# SAM3X_MCU2.net
KiCad netlist of a schematic drawn in Altium Designer
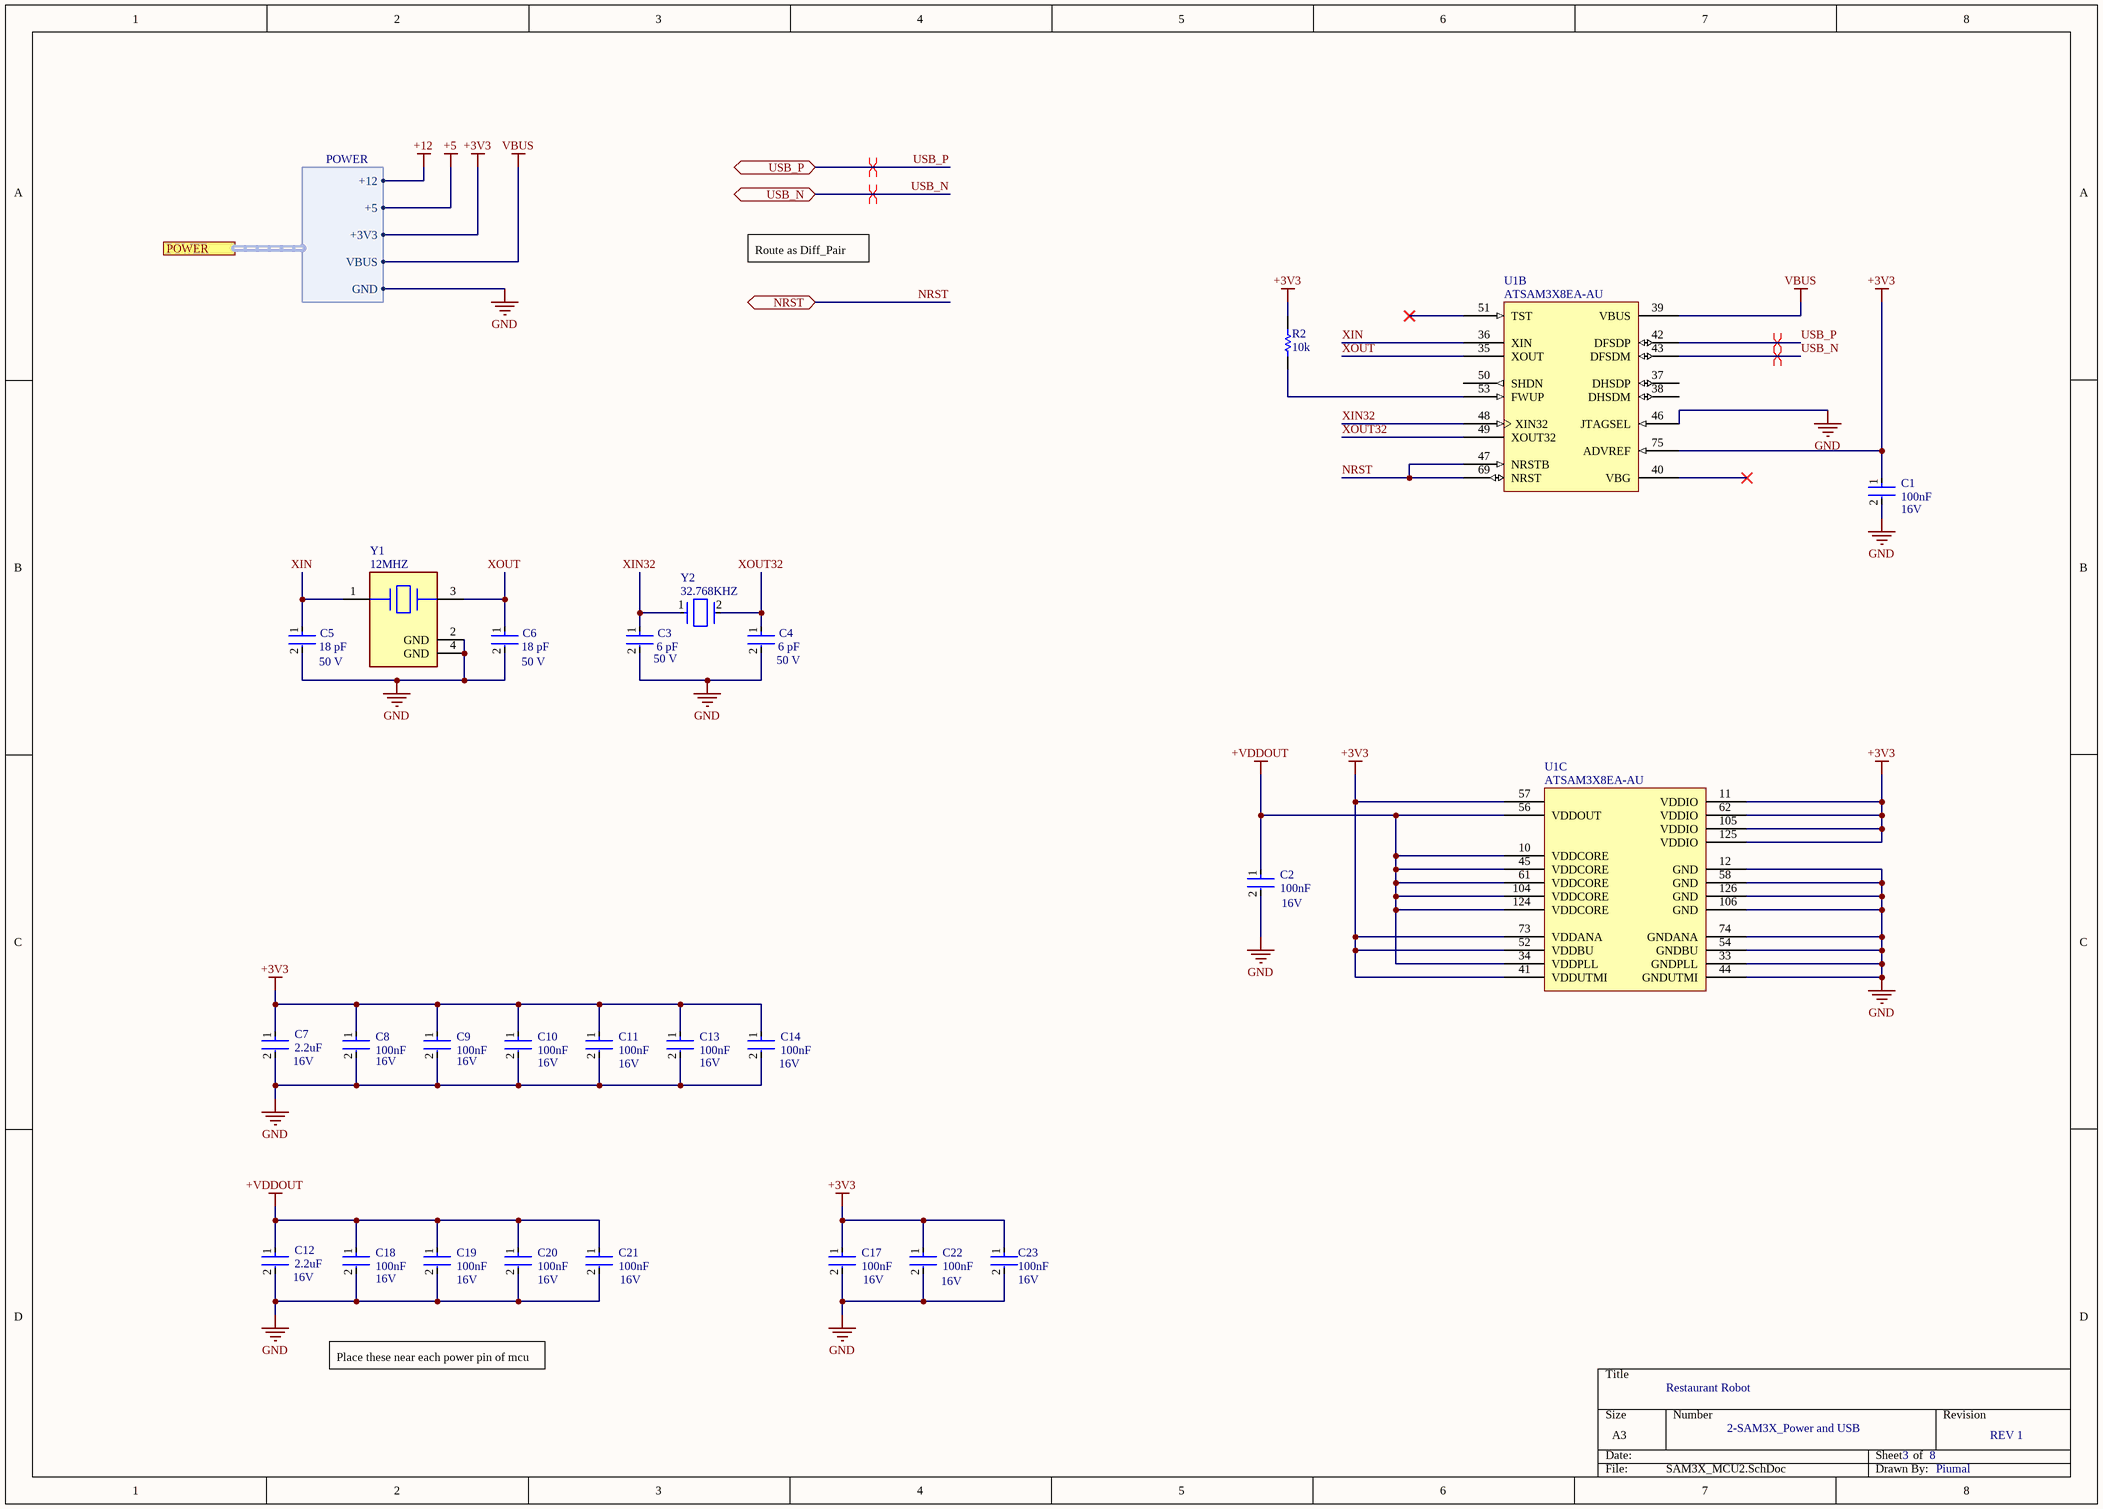
[diagram p0: SAM3X_MCU2.SchDoc]

(export (version "E")
  (design (tool "Eeschema 10.0.6"))
  (components
    (comp (ref "C1")
      (value "CL21B104KOANNNC")
      (footprint "FP-CL21-IPC_A")
      (description "CL21 Series 0805 100nF 16V ±10% Tolerance X7R Multilayer Ceramic Chip Capacitor")
      (fields
        (field (name "VOLTAGE RATING (DC)") "16V")
        (field (name "TOLERANCE") "10%")
        (field (name "CAPACITANCE") "100nF")
      )
      (libsource (lib "Altium Content Vault") (part "b4654b650e69147ec39a6b967a45e02"))
    )
    (comp (ref "C2")
      (value "CL21B104KOANNNC")
      (footprint "FP-CL21-IPC_A")
      (description "CL21 Series 0805 100nF 16V ±10% Tolerance X7R Multilayer Ceramic Chip Capacitor")
      (fields
        (field (name "VOLTAGE RATING (DC)") "16V")
        (field (name "TOLERANCE") "10%")
        (field (name "CAPACITANCE") "100nF")
      )
      (libsource (lib "Altium Content Vault") (part "b4654b650e69147ec39a6b967a45e02"))
    )
    (comp (ref "C3")
      (value "C0805C120J5GACTU")
      (footprint "FP-C0805C-DN-MFG")
      (description "CAP CER 12PF 50V C0G/NP0 0805")
      (fields
        (field (name "MANUFACTURER") "KEMET")
        (field (name "CAPACITANCE") "6 pF")
        (field (name "TOLERANCE") "0.05")
        (field (name "VOLTAGE RATING") "50 V")
      )
      (libsource (lib "Altium Content Vault") (part "b4654b650e69147ec39a6b967a45e02"))
    )
    (comp (ref "C4")
      (value "C0805C120J5GACTU")
      (footprint "FP-C0805C-DN-MFG")
      (description "CAP CER 12PF 50V C0G/NP0 0805")
      (fields
        (field (name "MANUFACTURER") "KEMET")
        (field (name "CAPACITANCE") "6 pF")
        (field (name "TOLERANCE") "0.05")
        (field (name "VOLTAGE RATING") "50 V")
      )
      (libsource (lib "Altium Content Vault") (part "b4654b650e69147ec39a6b967a45e02"))
    )
    (comp (ref "C5")
      (value "C0805C120J5GACTU")
      (footprint "FP-C0805C-DN-MFG")
      (description "CAP CER 12PF 50V C0G/NP0 0805")
      (fields
        (field (name "MANUFACTURER") "KEMET")
        (field (name "CAPACITANCE") "18 pF")
        (field (name "TOLERANCE") "0.05")
        (field (name "VOLTAGE RATING") "50 V")
      )
      (libsource (lib "Altium Content Vault") (part "b4654b650e69147ec39a6b967a45e02"))
    )
    (comp (ref "C6")
      (value "C0805C120J5GACTU")
      (footprint "FP-C0805C-DN-MFG")
      (description "CAP CER 12PF 50V C0G/NP0 0805")
      (fields
        (field (name "MANUFACTURER") "KEMET")
        (field (name "CAPACITANCE") "18 pF")
        (field (name "TOLERANCE") "0.05")
        (field (name "VOLTAGE RATING") "50 V")
      )
      (libsource (lib "Altium Content Vault") (part "b4654b650e69147ec39a6b967a45e02"))
    )
    (comp (ref "C7")
      (value "CL21A225KOFNNNG")
      (footprint "FP-CL21-IPC_A")
      (description "CL21 Series 0805 2.2uF 16V ±10% Tolerance X5R Multilayer Ceramic Chip Capacitor")
      (fields
        (field (name "VOLTAGE RATING") "16V")
        (field (name "TOLERANCE") "10%")
        (field (name "CAPACITANCE") "2.2uF")
      )
      (libsource (lib "Altium Content Vault") (part "b4654b650e69147ec39a6b967a45e02"))
    )
    (comp (ref "C8")
      (value "CL21B104KOANNNC")
      (footprint "FP-CL21-IPC_A")
      (description "CL21 Series 0805 100nF 16V ±10% Tolerance X7R Multilayer Ceramic Chip Capacitor")
      (fields
        (field (name "VOLTAGE RATING (DC)") "16V")
        (field (name "TOLERANCE") "10%")
        (field (name "CAPACITANCE") "100nF")
      )
      (libsource (lib "Altium Content Vault") (part "b4654b650e69147ec39a6b967a45e02"))
    )
    (comp (ref "C9")
      (value "CL21B104KOANNNC")
      (footprint "FP-CL21-IPC_A")
      (description "CL21 Series 0805 100nF 16V ±10% Tolerance X7R Multilayer Ceramic Chip Capacitor")
      (fields
        (field (name "VOLTAGE RATING (DC)") "16V")
        (field (name "TOLERANCE") "10%")
        (field (name "CAPACITANCE") "100nF")
      )
      (libsource (lib "Altium Content Vault") (part "b4654b650e69147ec39a6b967a45e02"))
    )
    (comp (ref "C10")
      (value "CL21B104KOANNNC")
      (footprint "FP-CL21-IPC_A")
      (description "CL21 Series 0805 100nF 16V ±10% Tolerance X7R Multilayer Ceramic Chip Capacitor")
      (fields
        (field (name "VOLTAGE RATING (DC)") "16V")
        (field (name "TOLERANCE") "10%")
        (field (name "CAPACITANCE") "100nF")
      )
      (libsource (lib "Altium Content Vault") (part "b4654b650e69147ec39a6b967a45e02"))
    )
    (comp (ref "C11")
      (value "CL21B104KOANNNC")
      (footprint "FP-CL21-IPC_A")
      (description "CL21 Series 0805 100nF 16V ±10% Tolerance X7R Multilayer Ceramic Chip Capacitor")
      (fields
        (field (name "VOLTAGE RATING (DC)") "16V")
        (field (name "TOLERANCE") "10%")
        (field (name "CAPACITANCE") "100nF")
      )
      (libsource (lib "Altium Content Vault") (part "b4654b650e69147ec39a6b967a45e02"))
    )
    (comp (ref "C12")
      (value "CL21A225KOFNNNG")
      (footprint "FP-CL21-IPC_A")
      (description "CL21 Series 0805 2.2uF 16V ±10% Tolerance X5R Multilayer Ceramic Chip Capacitor")
      (fields
        (field (name "VOLTAGE RATING") "16V")
        (field (name "TOLERANCE") "10%")
        (field (name "CAPACITANCE") "2.2uF")
      )
      (libsource (lib "Altium Content Vault") (part "b4654b650e69147ec39a6b967a45e02"))
    )
    (comp (ref "C13")
      (value "CL21B104KOANNNC")
      (footprint "FP-CL21-IPC_A")
      (description "CL21 Series 0805 100nF 16V ±10% Tolerance X7R Multilayer Ceramic Chip Capacitor")
      (fields
        (field (name "VOLTAGE RATING (DC)") "16V")
        (field (name "TOLERANCE") "10%")
        (field (name "CAPACITANCE") "100nF")
      )
      (libsource (lib "Altium Content Vault") (part "b4654b650e69147ec39a6b967a45e02"))
    )
    (comp (ref "C14")
      (value "CL21B104KOANNNC")
      (footprint "FP-CL21-IPC_A")
      (description "CL21 Series 0805 100nF 16V ±10% Tolerance X7R Multilayer Ceramic Chip Capacitor")
      (fields
        (field (name "VOLTAGE RATING (DC)") "16V")
        (field (name "TOLERANCE") "10%")
        (field (name "CAPACITANCE") "100nF")
      )
      (libsource (lib "Altium Content Vault") (part "b4654b650e69147ec39a6b967a45e02"))
    )
    (comp (ref "C17")
      (value "CL21B104KOANNNC")
      (footprint "FP-CL21-IPC_A")
      (description "CL21 Series 0805 100nF 16V ±10% Tolerance X7R Multilayer Ceramic Chip Capacitor")
      (fields
        (field (name "VOLTAGE RATING (DC)") "16V")
        (field (name "TOLERANCE") "10%")
        (field (name "CAPACITANCE") "100nF")
      )
      (libsource (lib "Altium Content Vault") (part "b4654b650e69147ec39a6b967a45e02"))
    )
    (comp (ref "C18")
      (value "CL21B104KOANNNC")
      (footprint "FP-CL21-IPC_A")
      (description "CL21 Series 0805 100nF 16V ±10% Tolerance X7R Multilayer Ceramic Chip Capacitor")
      (fields
        (field (name "VOLTAGE RATING (DC)") "16V")
        (field (name "TOLERANCE") "10%")
        (field (name "CAPACITANCE") "100nF")
      )
      (libsource (lib "Altium Content Vault") (part "b4654b650e69147ec39a6b967a45e02"))
    )
    (comp (ref "C19")
      (value "CL21B104KOANNNC")
      (footprint "FP-CL21-IPC_A")
      (description "CL21 Series 0805 100nF 16V ±10% Tolerance X7R Multilayer Ceramic Chip Capacitor")
      (fields
        (field (name "VOLTAGE RATING (DC)") "16V")
        (field (name "TOLERANCE") "10%")
        (field (name "CAPACITANCE") "100nF")
      )
      (libsource (lib "Altium Content Vault") (part "b4654b650e69147ec39a6b967a45e02"))
    )
    (comp (ref "C20")
      (value "CL21B104KOANNNC")
      (footprint "FP-CL21-IPC_A")
      (description "CL21 Series 0805 100nF 16V ±10% Tolerance X7R Multilayer Ceramic Chip Capacitor")
      (fields
        (field (name "VOLTAGE RATING (DC)") "16V")
        (field (name "TOLERANCE") "10%")
        (field (name "CAPACITANCE") "100nF")
      )
      (libsource (lib "Altium Content Vault") (part "b4654b650e69147ec39a6b967a45e02"))
    )
    (comp (ref "C21")
      (value "CL21B104KOANNNC")
      (footprint "FP-CL21-IPC_A")
      (description "CL21 Series 0805 100nF 16V ±10% Tolerance X7R Multilayer Ceramic Chip Capacitor")
      (fields
        (field (name "VOLTAGE RATING (DC)") "16V")
        (field (name "TOLERANCE") "10%")
        (field (name "CAPACITANCE") "100nF")
      )
      (libsource (lib "Altium Content Vault") (part "b4654b650e69147ec39a6b967a45e02"))
    )
    (comp (ref "C22")
      (value "CL21B104KOANNNC")
      (footprint "FP-CL21-IPC_A")
      (description "CL21 Series 0805 100nF 16V ±10% Tolerance X7R Multilayer Ceramic Chip Capacitor")
      (fields
        (field (name "VOLTAGE RATING (DC)") "16V")
        (field (name "TOLERANCE") "10%")
        (field (name "CAPACITANCE") "100nF")
      )
      (libsource (lib "Altium Content Vault") (part "b4654b650e69147ec39a6b967a45e02"))
    )
    (comp (ref "C23")
      (value "100nF")
      (footprint "FP-CL21-IPC_A")
      (description "CL21 Series 0805 100nF 16V ±10% Tolerance X7R Multilayer Ceramic Chip Capacitor")
      (fields
        (field (name "VOLTAGE RATING (DC)") "16V")
        (field (name "TOLERANCE") "10%")
        (field (name "Comment") "CL21B104KOANNNC")
      )
      (libsource (lib "Altium Content Vault") (part "b4654b650e69147ec39a6b967a45e02"))
    )
    (comp (ref "R2")
      (value "RC0805JR-0710KL")
      (footprint "RESC2013X60X35ML10T20")
      (description "Chip Resistor, 10 KOhm, +/- 5%, 0.125 W, -55 to 155 degC, 0805 (2012 Metric), RoHS, Tape and Reel")
      (fields (field (name "MANUFACTURER") "Yageo") (field (name "RESISTANCE") "10k"))
      (libsource (lib "Altium Content Vault") (part "RES-2"))
    )
    (comp (ref "U1")
      (value "ATSAM3X8EA-AU")
      (footprint "LQFP144_M")
      (fields (field (name "MANUFACTURER") "Atmel"))
      (libsource (lib "Altium Content Vault") (part "ATML-ATSAM3X-LQFP-144"))
    )
    (comp (ref "Y1")
      (value "12MHZ")
      (footprint "FP-ABM8G-MFG")
      (description "Crystal 12MHz ±20ppm (Tol) ±30ppm (Stability) 18pF FUND 120Ω 4-Pin SMD T/R")
      (fields (field (name "TOLERANCE") "20ppm"))
      (libsource (lib "Altium Content Vault") (part "48e526d86b7f2615d98721063c72f49"))
    )
    (comp (ref "Y2")
      (value "32.768KHZ")
      (footprint "FP-NX3215SA-MFG")
      (description "NX3215SA-32.768K-STD-MUA-14 Parallel - Fundamental Quartz Crystal, 0.032768MHz Nom")
      (libsource (lib "Altium Content Vault") (part "c23a69dc6c9e2f18f2079038eb95dd1"))
    )
  )
  (nets
    (net (code "2") (name "+3V3") (class "Default")
      (node (ref "C1") (pin "1") (pinfunction "1_1") (pintype "passive"))
      (node (ref "C10") (pin "1") (pinfunction "1_1") (pintype "passive"))
      (node (ref "C11") (pin "1") (pinfunction "1_1") (pintype "passive"))
      (node (ref "C13") (pin "1") (pinfunction "1_1") (pintype "passive"))
      (node (ref "C14") (pin "1") (pinfunction "1_1") (pintype "passive"))
      (node (ref "C17") (pin "1") (pinfunction "1_1") (pintype "passive"))
      (node (ref "C22") (pin "1") (pinfunction "1_1") (pintype "passive"))
      (node (ref "C23") (pin "1") (pinfunction "1_1") (pintype "passive"))
      (node (ref "C7") (pin "1") (pinfunction "1_1") (pintype "passive"))
      (node (ref "C8") (pin "1") (pinfunction "1_1") (pintype "passive"))
      (node (ref "C9") (pin "1") (pinfunction "1_1") (pintype "passive"))
      (node (ref "R2") (pin "2") (pinfunction "2_2") (pintype "passive"))
      (node (ref "U1") (pin "105") (pinfunction "VDDIO_105") (pintype "power_in"))
      (node (ref "U1") (pin "11") (pinfunction "VDDIO_11") (pintype "power_in"))
      (node (ref "U1") (pin "125") (pinfunction "VDDIO_125") (pintype "power_in"))
      (node (ref "U1") (pin "41") (pinfunction "VDDUTMI_41") (pintype "power_in"))
      (node (ref "U1") (pin "52") (pinfunction "VDDBU_52") (pintype "power_in"))
      (node (ref "U1") (pin "57") (pinfunction "VDDIN_57") (pintype "power_in"))
      (node (ref "U1") (pin "62") (pinfunction "VDDIO_62") (pintype "power_in"))
      (node (ref "U1") (pin "73") (pinfunction "VDDANA_73") (pintype "power_in"))
      (node (ref "U1") (pin "75") (pinfunction "ADVREF_75") (pintype "input"))
    )
    (net (code "5") (name "+VDDOUT") (class "Default")
      (node (ref "C12") (pin "1") (pinfunction "1_1") (pintype "passive"))
      (node (ref "C18") (pin "1") (pinfunction "1_1") (pintype "passive"))
      (node (ref "C19") (pin "1") (pinfunction "1_1") (pintype "passive"))
      (node (ref "C2") (pin "1") (pinfunction "1_1") (pintype "passive"))
      (node (ref "C20") (pin "1") (pinfunction "1_1") (pintype "passive"))
      (node (ref "C21") (pin "1") (pinfunction "1_1") (pintype "passive"))
      (node (ref "U1") (pin "10") (pinfunction "VDDCORE_10") (pintype "power_in"))
      (node (ref "U1") (pin "104") (pinfunction "VDDCORE_104") (pintype "power_in"))
      (node (ref "U1") (pin "124") (pinfunction "VDDCORE_124") (pintype "power_in"))
      (node (ref "U1") (pin "34") (pinfunction "VDDPLL_34") (pintype "power_in"))
      (node (ref "U1") (pin "45") (pinfunction "VDDCORE_45") (pintype "power_in"))
      (node (ref "U1") (pin "56") (pinfunction "VDDOUT_56") (pintype "power_in"))
      (node (ref "U1") (pin "61") (pinfunction "VDDCORE_61") (pintype "power_in"))
    )
    (net (code "6") (name "/NRST") (class "Default")
      (node (ref "U1") (pin "47") (pinfunction "NRSTB_47") (pintype "input"))
      (node (ref "U1") (pin "69") (pinfunction "NRST_69") (pintype "bidirectional"))
    )
    (net (code "7") (name "/USB_N") (class "Default")
      (node (ref "U1") (pin "43") (pinfunction "DFSDM_43") (pintype "bidirectional"))
    )
    (net (code "8") (name "/USB_P") (class "Default")
      (node (ref "U1") (pin "42") (pinfunction "DFSDP_42") (pintype "bidirectional"))
    )
    (net (code "9") (name "/XIN") (class "Default")
      (node (ref "C5") (pin "1") (pinfunction "1_1") (pintype "passive"))
      (node (ref "U1") (pin "36") (pinfunction "XIN_36") (pintype "passive"))
      (node (ref "Y1") (pin "1") (pinfunction "1_1") (pintype "passive"))
    )
    (net (code "10") (name "/XIN32") (class "Default")
      (node (ref "C3") (pin "1") (pinfunction "1_1") (pintype "passive"))
      (node (ref "U1") (pin "48") (pinfunction "XIN32_48") (pintype "input"))
      (node (ref "Y2") (pin "1") (pinfunction "1_1") (pintype "passive"))
    )
    (net (code "11") (name "/XOUT") (class "Default")
      (node (ref "C6") (pin "1") (pinfunction "1_1") (pintype "passive"))
      (node (ref "U1") (pin "35") (pinfunction "XOUT_35") (pintype "passive"))
      (node (ref "Y1") (pin "3") (pinfunction "3_3") (pintype "passive"))
    )
    (net (code "12") (name "/XOUT32") (class "Default")
      (node (ref "C4") (pin "1") (pinfunction "1_1") (pintype "passive"))
      (node (ref "U1") (pin "49") (pinfunction "XOUT32_49") (pintype "passive"))
      (node (ref "Y2") (pin "2") (pinfunction "2_2") (pintype "passive"))
    )
    (net (code "14") (name "GND") (class "Default")
      (node (ref "C1") (pin "2") (pinfunction "2_2") (pintype "passive"))
      (node (ref "C10") (pin "2") (pinfunction "2_2") (pintype "passive"))
      (node (ref "C11") (pin "2") (pinfunction "2_2") (pintype "passive"))
      (node (ref "C12") (pin "2") (pinfunction "2_2") (pintype "passive"))
      (node (ref "C13") (pin "2") (pinfunction "2_2") (pintype "passive"))
      (node (ref "C14") (pin "2") (pinfunction "2_2") (pintype "passive"))
      (node (ref "C17") (pin "2") (pinfunction "2_2") (pintype "passive"))
      (node (ref "C18") (pin "2") (pinfunction "2_2") (pintype "passive"))
      (node (ref "C19") (pin "2") (pinfunction "2_2") (pintype "passive"))
      (node (ref "C2") (pin "2") (pinfunction "2_2") (pintype "passive"))
      (node (ref "C20") (pin "2") (pinfunction "2_2") (pintype "passive"))
      (node (ref "C21") (pin "2") (pinfunction "2_2") (pintype "passive"))
      (node (ref "C22") (pin "2") (pinfunction "2_2") (pintype "passive"))
      (node (ref "C23") (pin "2") (pinfunction "2_2") (pintype "passive"))
      (node (ref "C3") (pin "2") (pinfunction "2_2") (pintype "passive"))
      (node (ref "C4") (pin "2") (pinfunction "2_2") (pintype "passive"))
      (node (ref "C5") (pin "2") (pinfunction "2_2") (pintype "passive"))
      (node (ref "C6") (pin "2") (pinfunction "2_2") (pintype "passive"))
      (node (ref "C7") (pin "2") (pinfunction "2_2") (pintype "passive"))
      (node (ref "C8") (pin "2") (pinfunction "2_2") (pintype "passive"))
      (node (ref "C9") (pin "2") (pinfunction "2_2") (pintype "passive"))
      (node (ref "U1") (pin "106") (pinfunction "GND_106") (pintype "power_in"))
      (node (ref "U1") (pin "12") (pinfunction "GND_12") (pintype "power_in"))
      (node (ref "U1") (pin "126") (pinfunction "GND_126") (pintype "power_in"))
      (node (ref "U1") (pin "33") (pinfunction "GNDPLL_33") (pintype "power_in"))
      (node (ref "U1") (pin "44") (pinfunction "GNDUTMI_44") (pintype "power_in"))
      (node (ref "U1") (pin "46") (pinfunction "JTAGSEL_46") (pintype "input"))
      (node (ref "U1") (pin "54") (pinfunction "GNDBU_54") (pintype "power_in"))
      (node (ref "U1") (pin "58") (pinfunction "GND_58") (pintype "power_in"))
      (node (ref "U1") (pin "74") (pinfunction "GNDANA_74") (pintype "power_in"))
      (node (ref "Y1") (pin "2") (pinfunction "GND_2") (pintype "passive"))
      (node (ref "Y1") (pin "4") (pinfunction "GND_4") (pintype "passive"))
    )
    (net (code "15") (name "Net-(U1B-FWUP)") (class "Default")
      (node (ref "R2") (pin "1") (pinfunction "1_1") (pintype "passive"))
      (node (ref "U1") (pin "53") (pinfunction "FWUP_53") (pintype "input"))
    )
    (net (code "16") (name "VBUS") (class "Default")
      (node (ref "U1") (pin "39") (pinfunction "VBUS_39") (pintype "passive"))
    )
    (net (code "17") (name "unconnected-(U1B-DHSDM-Pad38)") (class "Default")
      (node (ref "U1") (pin "38") (pinfunction "DHSDM_38") (pintype "bidirectional"))
    )
    (net (code "18") (name "unconnected-(U1B-DHSDP-Pad37)") (class "Default")
      (node (ref "U1") (pin "37") (pinfunction "DHSDP_37") (pintype "bidirectional"))
    )
    (net (code "19") (name "unconnected-(U1B-SHDN-Pad50)") (class "Default")
      (node (ref "U1") (pin "50") (pinfunction "SHDN_50") (pintype "output"))
    )
    (net (code "20") (name "unconnected-(U1B-TST-Pad51)") (class "Default")
      (node (ref "U1") (pin "51") (pinfunction "TST_51") (pintype "input+no_connect"))
    )
    (net (code "21") (name "unconnected-(U1B-VBG-Pad40)") (class "Default")
      (node (ref "U1") (pin "40") (pinfunction "VBG_40") (pintype "passive+no_connect"))
    )
  )
)
